# RFR24_AMS_Design_-_Fuses_V1.net
KiCad netlist of a schematic drawn in Altium Designer
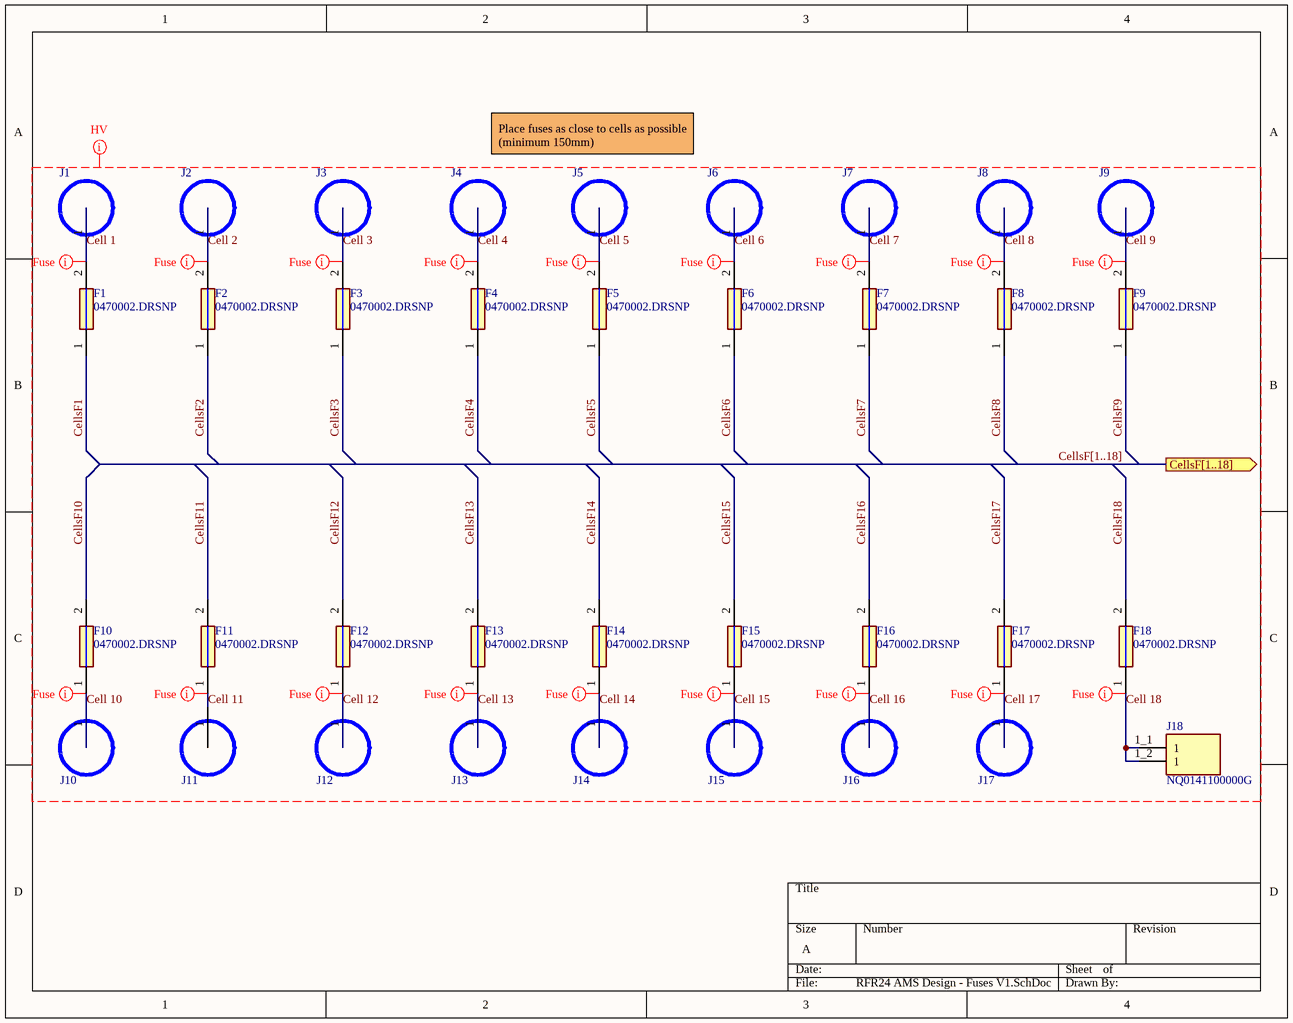
[diagram p0: RFR24 AMS Design - Fuses V1.SchDoc]

(export (version "E")
  (design (tool "Eeschema 10.0.6"))
  (components
    (comp (ref "F1")
      (value "0470002.DRSNP")
      (footprint "SamacSys:0470002DRSNP")
      (description "Fuse")
      (fields (field (name "MOUSER PART NUMBER") "576-0470002.DRSNP"))
      (libsource (lib "*") (part "0470002.DRSNP"))
    )
    (comp (ref "F2")
      (value "0470002.DRSNP")
      (footprint "SamacSys:0470002DRSNP")
      (description "Fuse")
      (fields (field (name "MOUSER PART NUMBER") "576-0470002.DRSNP"))
      (libsource (lib "*") (part "0470002.DRSNP"))
    )
    (comp (ref "F3")
      (value "0470002.DRSNP")
      (footprint "SamacSys:0470002DRSNP")
      (description "Fuse")
      (fields (field (name "MOUSER PART NUMBER") "576-0470002.DRSNP"))
      (libsource (lib "*") (part "0470002.DRSNP"))
    )
    (comp (ref "F4")
      (value "0470002.DRSNP")
      (footprint "SamacSys:0470002DRSNP")
      (description "Fuse")
      (fields (field (name "MOUSER PART NUMBER") "576-0470002.DRSNP"))
      (libsource (lib "*") (part "0470002.DRSNP"))
    )
    (comp (ref "F5")
      (value "0470002.DRSNP")
      (footprint "SamacSys:0470002DRSNP")
      (description "Fuse")
      (fields (field (name "MOUSER PART NUMBER") "576-0470002.DRSNP"))
      (libsource (lib "*") (part "0470002.DRSNP"))
    )
    (comp (ref "F6")
      (value "0470002.DRSNP")
      (footprint "SamacSys:0470002DRSNP")
      (description "Fuse")
      (fields (field (name "MOUSER PART NUMBER") "576-0470002.DRSNP"))
      (libsource (lib "*") (part "0470002.DRSNP"))
    )
    (comp (ref "F7")
      (value "0470002.DRSNP")
      (footprint "SamacSys:0470002DRSNP")
      (description "Fuse")
      (fields (field (name "MOUSER PART NUMBER") "576-0470002.DRSNP"))
      (libsource (lib "*") (part "0470002.DRSNP"))
    )
    (comp (ref "F8")
      (value "0470002.DRSNP")
      (footprint "SamacSys:0470002DRSNP")
      (description "Fuse")
      (fields (field (name "MOUSER PART NUMBER") "576-0470002.DRSNP"))
      (libsource (lib "*") (part "0470002.DRSNP"))
    )
    (comp (ref "F9")
      (value "0470002.DRSNP")
      (footprint "SamacSys:0470002DRSNP")
      (description "Fuse")
      (fields (field (name "MOUSER PART NUMBER") "576-0470002.DRSNP"))
      (libsource (lib "*") (part "0470002.DRSNP"))
    )
    (comp (ref "F10")
      (value "0470002.DRSNP")
      (footprint "SamacSys:0470002DRSNP")
      (description "Fuse")
      (fields (field (name "MOUSER PART NUMBER") "576-0470002.DRSNP"))
      (libsource (lib "*") (part "0470002.DRSNP"))
    )
    (comp (ref "F11")
      (value "0470002.DRSNP")
      (footprint "SamacSys:0470002DRSNP")
      (description "Fuse")
      (fields (field (name "MOUSER PART NUMBER") "576-0470002.DRSNP"))
      (libsource (lib "*") (part "0470002.DRSNP"))
    )
    (comp (ref "F12")
      (value "0470002.DRSNP")
      (footprint "SamacSys:0470002DRSNP")
      (description "Fuse")
      (fields (field (name "MOUSER PART NUMBER") "576-0470002.DRSNP"))
      (libsource (lib "*") (part "0470002.DRSNP"))
    )
    (comp (ref "F13")
      (value "0470002.DRSNP")
      (footprint "SamacSys:0470002DRSNP")
      (description "Fuse")
      (fields (field (name "MOUSER PART NUMBER") "576-0470002.DRSNP"))
      (libsource (lib "*") (part "0470002.DRSNP"))
    )
    (comp (ref "F14")
      (value "0470002.DRSNP")
      (footprint "SamacSys:0470002DRSNP")
      (description "Fuse")
      (fields (field (name "MOUSER PART NUMBER") "576-0470002.DRSNP"))
      (libsource (lib "*") (part "0470002.DRSNP"))
    )
    (comp (ref "F15")
      (value "0470002.DRSNP")
      (footprint "SamacSys:0470002DRSNP")
      (description "Fuse")
      (fields (field (name "MOUSER PART NUMBER") "576-0470002.DRSNP"))
      (libsource (lib "*") (part "0470002.DRSNP"))
    )
    (comp (ref "F16")
      (value "0470002.DRSNP")
      (footprint "SamacSys:0470002DRSNP")
      (description "Fuse")
      (fields (field (name "MOUSER PART NUMBER") "576-0470002.DRSNP"))
      (libsource (lib "*") (part "0470002.DRSNP"))
    )
    (comp (ref "F17")
      (value "0470002.DRSNP")
      (footprint "SamacSys:0470002DRSNP")
      (description "Fuse")
      (fields (field (name "MOUSER PART NUMBER") "576-0470002.DRSNP"))
      (libsource (lib "*") (part "0470002.DRSNP"))
    )
    (comp (ref "F18")
      (value "0470002.DRSNP")
      (footprint "SamacSys:0470002DRSNP")
      (description "Fuse")
      (fields (field (name "MOUSER PART NUMBER") "576-0470002.DRSNP"))
      (libsource (lib "*") (part "0470002.DRSNP"))
    )
    (comp (ref "J1")
      (value "2900-3-15-20-75-14-11-0")
      (footprint "2900-3-15-20-75-14-11-0-Footprint-1")
      (description "https://www.mouser.com/datasheet/2/273/Mil_Max_7_10_2023_2900_3_15_20_75_14_11_0_DSL-3236111.pdf")
      (libsource (lib "Rutgers University") (part "2900-3-15-20-75-14-11-0-Symbol-1"))
    )
    (comp (ref "J2")
      (value "2900-3-15-20-75-14-11-0")
      (footprint "2900-3-15-20-75-14-11-0-Footprint-1")
      (description "https://www.mouser.com/datasheet/2/273/Mil_Max_7_10_2023_2900_3_15_20_75_14_11_0_DSL-3236111.pdf")
      (libsource (lib "Rutgers University") (part "2900-3-15-20-75-14-11-0-Symbol-1"))
    )
    (comp (ref "J3")
      (value "2900-3-15-20-75-14-11-0")
      (footprint "2900-3-15-20-75-14-11-0-Footprint-1")
      (description "https://www.mouser.com/datasheet/2/273/Mil_Max_7_10_2023_2900_3_15_20_75_14_11_0_DSL-3236111.pdf")
      (libsource (lib "Rutgers University") (part "2900-3-15-20-75-14-11-0-Symbol-1"))
    )
    (comp (ref "J4")
      (value "2900-3-15-20-75-14-11-0")
      (footprint "2900-3-15-20-75-14-11-0-Footprint-1")
      (description "https://www.mouser.com/datasheet/2/273/Mil_Max_7_10_2023_2900_3_15_20_75_14_11_0_DSL-3236111.pdf")
      (libsource (lib "Rutgers University") (part "2900-3-15-20-75-14-11-0-Symbol-1"))
    )
    (comp (ref "J5")
      (value "2900-3-15-20-75-14-11-0")
      (footprint "2900-3-15-20-75-14-11-0-Footprint-1")
      (description "https://www.mouser.com/datasheet/2/273/Mil_Max_7_10_2023_2900_3_15_20_75_14_11_0_DSL-3236111.pdf")
      (libsource (lib "Rutgers University") (part "2900-3-15-20-75-14-11-0-Symbol-1"))
    )
    (comp (ref "J6")
      (value "2900-3-15-20-75-14-11-0")
      (footprint "2900-3-15-20-75-14-11-0-Footprint-1")
      (description "https://www.mouser.com/datasheet/2/273/Mil_Max_7_10_2023_2900_3_15_20_75_14_11_0_DSL-3236111.pdf")
      (libsource (lib "Rutgers University") (part "2900-3-15-20-75-14-11-0-Symbol-1"))
    )
    (comp (ref "J7")
      (value "2900-3-15-20-75-14-11-0")
      (footprint "2900-3-15-20-75-14-11-0-Footprint-1")
      (description "https://www.mouser.com/datasheet/2/273/Mil_Max_7_10_2023_2900_3_15_20_75_14_11_0_DSL-3236111.pdf")
      (libsource (lib "Rutgers University") (part "2900-3-15-20-75-14-11-0-Symbol-1"))
    )
    (comp (ref "J8")
      (value "2900-3-15-20-75-14-11-0")
      (footprint "2900-3-15-20-75-14-11-0-Footprint-1")
      (description "https://www.mouser.com/datasheet/2/273/Mil_Max_7_10_2023_2900_3_15_20_75_14_11_0_DSL-3236111.pdf")
      (libsource (lib "Rutgers University") (part "2900-3-15-20-75-14-11-0-Symbol-1"))
    )
    (comp (ref "J9")
      (value "2900-3-15-20-75-14-11-0")
      (footprint "2900-3-15-20-75-14-11-0-Footprint-1")
      (description "https://www.mouser.com/datasheet/2/273/Mil_Max_7_10_2023_2900_3_15_20_75_14_11_0_DSL-3236111.pdf")
      (libsource (lib "Rutgers University") (part "2900-3-15-20-75-14-11-0-Symbol-1"))
    )
    (comp (ref "J10")
      (value "2900-3-15-20-75-14-11-0")
      (footprint "2900-3-15-20-75-14-11-0-Footprint-1")
      (description "https://www.mouser.com/datasheet/2/273/Mil_Max_7_10_2023_2900_3_15_20_75_14_11_0_DSL-3236111.pdf")
      (libsource (lib "Rutgers University") (part "2900-3-15-20-75-14-11-0-Symbol-1"))
    )
    (comp (ref "J11")
      (value "2900-3-15-20-75-14-11-0")
      (footprint "2900-3-15-20-75-14-11-0-Footprint-1")
      (description "https://www.mouser.com/datasheet/2/273/Mil_Max_7_10_2023_2900_3_15_20_75_14_11_0_DSL-3236111.pdf")
      (libsource (lib "Rutgers University") (part "2900-3-15-20-75-14-11-0-Symbol-1"))
    )
    (comp (ref "J12")
      (value "2900-3-15-20-75-14-11-0")
      (footprint "2900-3-15-20-75-14-11-0-Footprint-1")
      (description "https://www.mouser.com/datasheet/2/273/Mil_Max_7_10_2023_2900_3_15_20_75_14_11_0_DSL-3236111.pdf")
      (libsource (lib "Rutgers University") (part "2900-3-15-20-75-14-11-0-Symbol-1"))
    )
    (comp (ref "J13")
      (value "2900-3-15-20-75-14-11-0")
      (footprint "2900-3-15-20-75-14-11-0-Footprint-1")
      (description "https://www.mouser.com/datasheet/2/273/Mil_Max_7_10_2023_2900_3_15_20_75_14_11_0_DSL-3236111.pdf")
      (libsource (lib "Rutgers University") (part "2900-3-15-20-75-14-11-0-Symbol-1"))
    )
    (comp (ref "J14")
      (value "2900-3-15-20-75-14-11-0")
      (footprint "2900-3-15-20-75-14-11-0-Footprint-1")
      (description "https://www.mouser.com/datasheet/2/273/Mil_Max_7_10_2023_2900_3_15_20_75_14_11_0_DSL-3236111.pdf")
      (libsource (lib "Rutgers University") (part "2900-3-15-20-75-14-11-0-Symbol-1"))
    )
    (comp (ref "J15")
      (value "2900-3-15-20-75-14-11-0")
      (footprint "2900-3-15-20-75-14-11-0-Footprint-1")
      (description "https://www.mouser.com/datasheet/2/273/Mil_Max_7_10_2023_2900_3_15_20_75_14_11_0_DSL-3236111.pdf")
      (libsource (lib "Rutgers University") (part "2900-3-15-20-75-14-11-0-Symbol-1"))
    )
    (comp (ref "J16")
      (value "2900-3-15-20-75-14-11-0")
      (footprint "2900-3-15-20-75-14-11-0-Footprint-1")
      (description "https://www.mouser.com/datasheet/2/273/Mil_Max_7_10_2023_2900_3_15_20_75_14_11_0_DSL-3236111.pdf")
      (libsource (lib "Rutgers University") (part "2900-3-15-20-75-14-11-0-Symbol-1"))
    )
    (comp (ref "J17")
      (value "2900-3-15-20-75-14-11-0")
      (footprint "2900-3-15-20-75-14-11-0-Footprint-1")
      (description "https://www.mouser.com/datasheet/2/273/Mil_Max_7_10_2023_2900_3_15_20_75_14_11_0_DSL-3236111.pdf")
      (libsource (lib "Rutgers University") (part "2900-3-15-20-75-14-11-0-Symbol-1"))
    )
    (comp (ref "J18")
      (value "NQ0141100000G")
      (footprint "AMPHENOL_NQ0141100000G")
      (description "1 Position Wire to Board Terminal Block Horizontal with Board Surface Mount")
      (fields (field (name "MF") "Amphenol Anytek"))
      (libsource (lib "NQ0141100000G") (part "NQ0141100000G"))
    )
  )
  (nets
    (net (code "1") (name "/Cell 1") (class "Default")
      (node (ref "F1") (pin "2") (pinfunction "2_2") (pintype "passive"))
      (node (ref "J1") (pin "1") (pinfunction "2_1") (pintype "passive"))
    )
    (net (code "2") (name "/Cell 2") (class "Default")
      (node (ref "F2") (pin "2") (pinfunction "2_2") (pintype "passive"))
      (node (ref "J2") (pin "1") (pinfunction "2_1") (pintype "passive"))
    )
    (net (code "3") (name "/Cell 3") (class "Default")
      (node (ref "F3") (pin "2") (pinfunction "2_2") (pintype "passive"))
      (node (ref "J3") (pin "1") (pinfunction "2_1") (pintype "passive"))
    )
    (net (code "4") (name "/Cell 4") (class "Default")
      (node (ref "F4") (pin "2") (pinfunction "2_2") (pintype "passive"))
      (node (ref "J4") (pin "1") (pinfunction "2_1") (pintype "passive"))
    )
    (net (code "5") (name "/Cell 5") (class "Default")
      (node (ref "F5") (pin "2") (pinfunction "2_2") (pintype "passive"))
      (node (ref "J5") (pin "1") (pinfunction "2_1") (pintype "passive"))
    )
    (net (code "6") (name "/Cell 6") (class "Default")
      (node (ref "F6") (pin "2") (pinfunction "2_2") (pintype "passive"))
      (node (ref "J6") (pin "1") (pinfunction "2_1") (pintype "passive"))
    )
    (net (code "7") (name "/Cell 7") (class "Default")
      (node (ref "F7") (pin "2") (pinfunction "2_2") (pintype "passive"))
      (node (ref "J7") (pin "1") (pinfunction "2_1") (pintype "passive"))
    )
    (net (code "8") (name "/Cell 8") (class "Default")
      (node (ref "F8") (pin "2") (pinfunction "2_2") (pintype "passive"))
      (node (ref "J8") (pin "1") (pinfunction "2_1") (pintype "passive"))
    )
    (net (code "9") (name "/Cell 9") (class "Default")
      (node (ref "F9") (pin "2") (pinfunction "2_2") (pintype "passive"))
      (node (ref "J9") (pin "1") (pinfunction "2_1") (pintype "passive"))
    )
    (net (code "10") (name "/Cell 10") (class "Default")
      (node (ref "F10") (pin "1") (pinfunction "1_1") (pintype "passive"))
      (node (ref "J10") (pin "1") (pinfunction "2_1") (pintype "passive"))
    )
    (net (code "11") (name "/Cell 11") (class "Default")
      (node (ref "F11") (pin "1") (pinfunction "1_1") (pintype "passive"))
      (node (ref "J11") (pin "1") (pinfunction "2_1") (pintype "passive"))
    )
    (net (code "12") (name "/Cell 12") (class "Default")
      (node (ref "F12") (pin "1") (pinfunction "1_1") (pintype "passive"))
      (node (ref "J12") (pin "1") (pinfunction "2_1") (pintype "passive"))
    )
    (net (code "13") (name "/Cell 13") (class "Default")
      (node (ref "F13") (pin "1") (pinfunction "1_1") (pintype "passive"))
      (node (ref "J13") (pin "1") (pinfunction "2_1") (pintype "passive"))
    )
    (net (code "14") (name "/Cell 14") (class "Default")
      (node (ref "F14") (pin "1") (pinfunction "1_1") (pintype "passive"))
      (node (ref "J14") (pin "1") (pinfunction "2_1") (pintype "passive"))
    )
    (net (code "15") (name "/Cell 15") (class "Default")
      (node (ref "F15") (pin "1") (pinfunction "1_1") (pintype "passive"))
      (node (ref "J15") (pin "1") (pinfunction "2_1") (pintype "passive"))
    )
    (net (code "16") (name "/Cell 16") (class "Default")
      (node (ref "F16") (pin "1") (pinfunction "1_1") (pintype "passive"))
      (node (ref "J16") (pin "1") (pinfunction "2_1") (pintype "passive"))
    )
    (net (code "17") (name "/Cell 17") (class "Default")
      (node (ref "F17") (pin "1") (pinfunction "1_1") (pintype "passive"))
      (node (ref "J17") (pin "1") (pinfunction "2_1") (pintype "passive"))
    )
    (net (code "18") (name "/Cell 18") (class "Default")
      (node (ref "F18") (pin "1") (pinfunction "1_1") (pintype "passive"))
      (node (ref "J18") (pin "1_1") (pinfunction "1_1_1") (pintype "passive"))
      (node (ref "J18") (pin "1_2") (pinfunction "1_1_2") (pintype "passive"))
    )
    (net (code "19") (name "/CellsF1") (class "Default")
      (node (ref "F1") (pin "1") (pinfunction "1_1") (pintype "passive"))
    )
    (net (code "20") (name "/CellsF2") (class "Default")
      (node (ref "F2") (pin "1") (pinfunction "1_1") (pintype "passive"))
    )
    (net (code "21") (name "/CellsF3") (class "Default")
      (node (ref "F3") (pin "1") (pinfunction "1_1") (pintype "passive"))
    )
    (net (code "22") (name "/CellsF4") (class "Default")
      (node (ref "F4") (pin "1") (pinfunction "1_1") (pintype "passive"))
    )
    (net (code "23") (name "/CellsF5") (class "Default")
      (node (ref "F5") (pin "1") (pinfunction "1_1") (pintype "passive"))
    )
    (net (code "24") (name "/CellsF6") (class "Default")
      (node (ref "F6") (pin "1") (pinfunction "1_1") (pintype "passive"))
    )
    (net (code "25") (name "/CellsF7") (class "Default")
      (node (ref "F7") (pin "1") (pinfunction "1_1") (pintype "passive"))
    )
    (net (code "26") (name "/CellsF8") (class "Default")
      (node (ref "F8") (pin "1") (pinfunction "1_1") (pintype "passive"))
    )
    (net (code "27") (name "/CellsF9") (class "Default")
      (node (ref "F9") (pin "1") (pinfunction "1_1") (pintype "passive"))
    )
    (net (code "28") (name "/CellsF10") (class "Default")
      (node (ref "F10") (pin "2") (pinfunction "2_2") (pintype "passive"))
    )
    (net (code "29") (name "/CellsF11") (class "Default")
      (node (ref "F11") (pin "2") (pinfunction "2_2") (pintype "passive"))
    )
    (net (code "30") (name "/CellsF12") (class "Default")
      (node (ref "F12") (pin "2") (pinfunction "2_2") (pintype "passive"))
    )
    (net (code "31") (name "/CellsF13") (class "Default")
      (node (ref "F13") (pin "2") (pinfunction "2_2") (pintype "passive"))
    )
    (net (code "32") (name "/CellsF14") (class "Default")
      (node (ref "F14") (pin "2") (pinfunction "2_2") (pintype "passive"))
    )
    (net (code "33") (name "/CellsF15") (class "Default")
      (node (ref "F15") (pin "2") (pinfunction "2_2") (pintype "passive"))
    )
    (net (code "34") (name "/CellsF16") (class "Default")
      (node (ref "F16") (pin "2") (pinfunction "2_2") (pintype "passive"))
    )
    (net (code "35") (name "/CellsF17") (class "Default")
      (node (ref "F17") (pin "2") (pinfunction "2_2") (pintype "passive"))
    )
    (net (code "36") (name "/CellsF18") (class "Default")
      (node (ref "F18") (pin "2") (pinfunction "2_2") (pintype "passive"))
    )
  )
)
